# Sheet2.net
KiCad netlist of a schematic drawn in Altium Designer
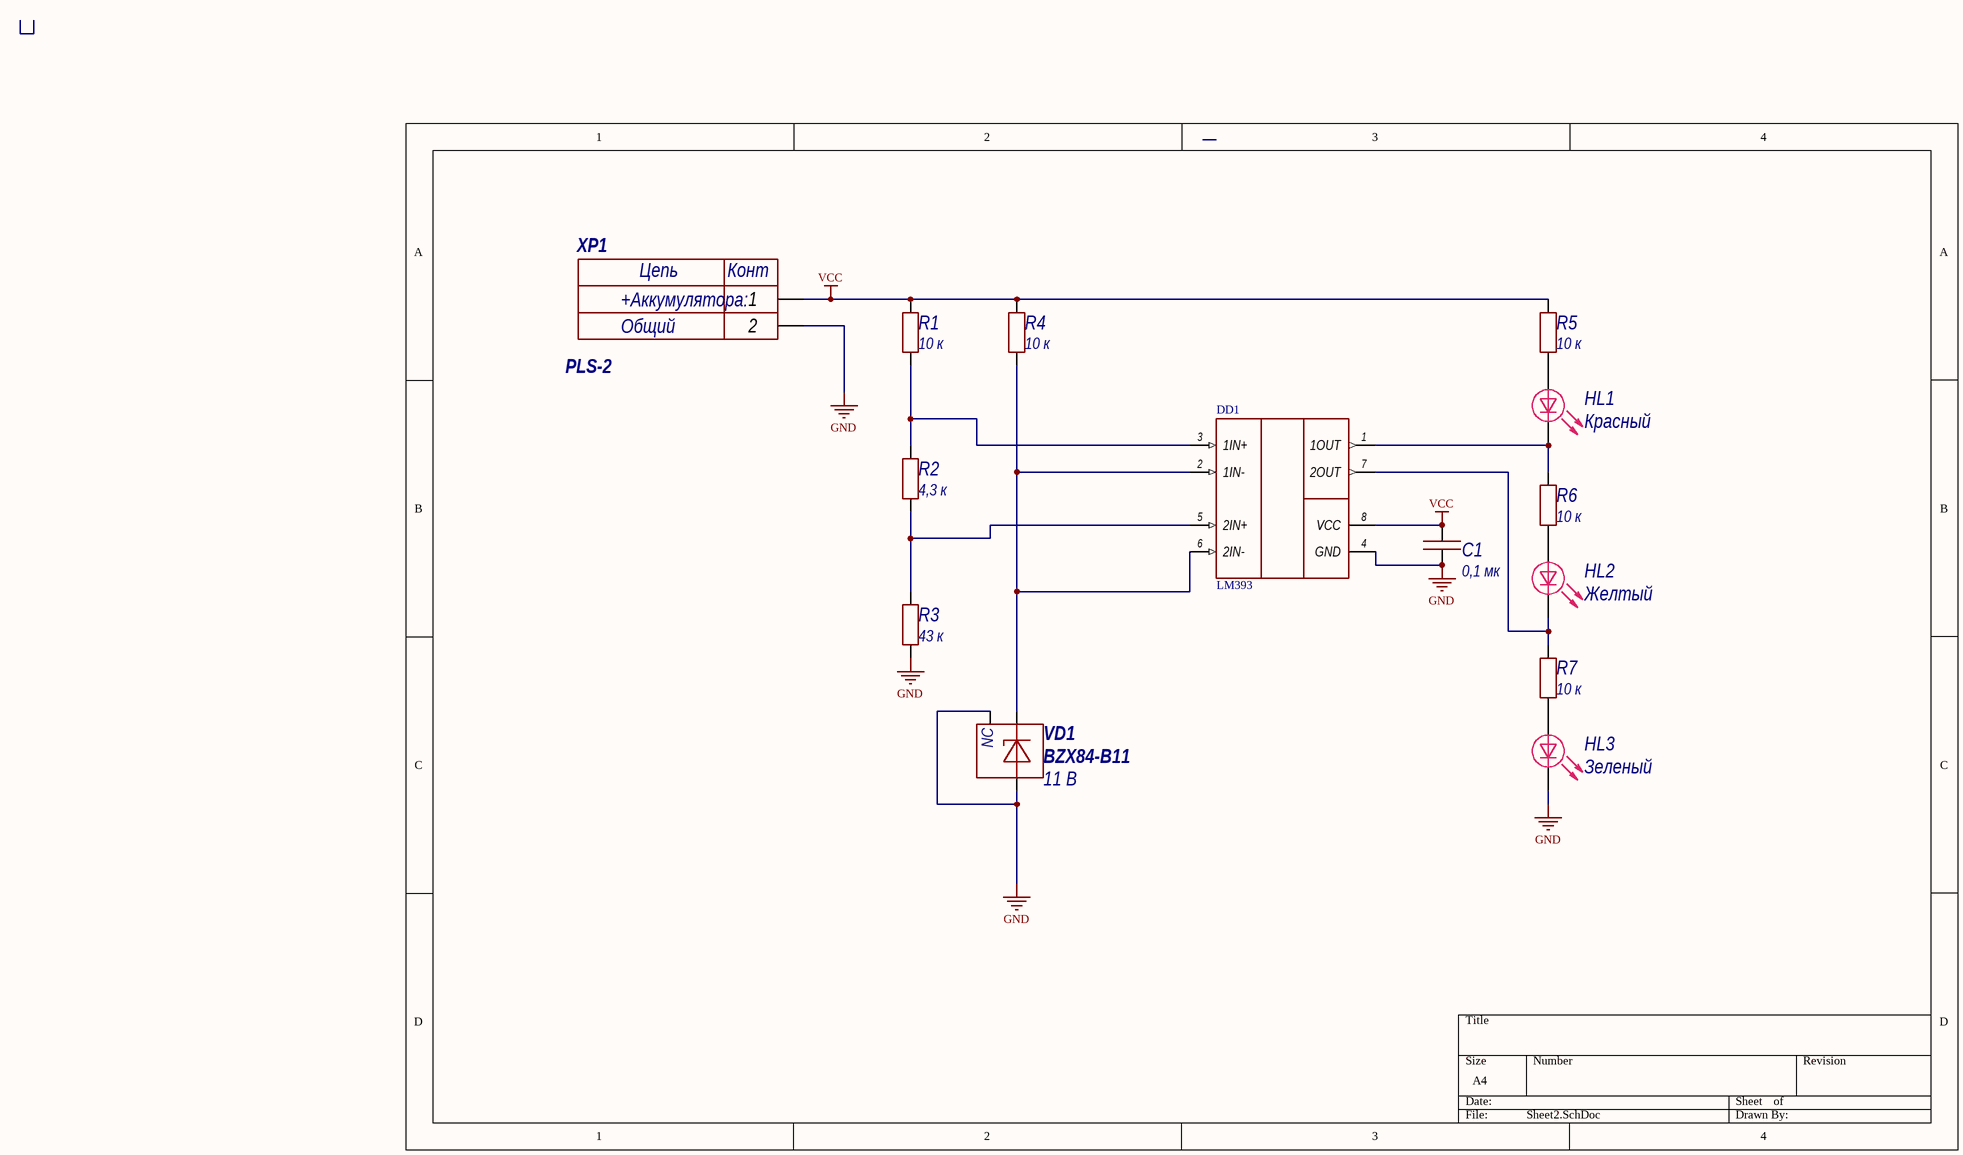
[diagram p0: Sheet2.SchDoc]

(export (version "E")
  (design (tool "Eeschema 10.0.6"))
  (components
    (comp (ref "C1")
      (value "0,1 мк")
      (footprint "0603C")
      (description "Конденсатор 0603C ёмкостью 0,1 мк 10%, 50 В, X7R")
      (fields (field (name "PART NUMBER") "Capacitor_0,1u_10_50V_X7R_0603C") (field (name "TOLERANCE") "10%"))
      (libsource (lib "Hydrolib") (part "Capacitor"))
    )
    (comp (ref "DD1")
      (value "LM393")
      (footprint "SOIC-8")
      (description "Двойной маломощный компаратор напряжения")
      (fields (field (name "MF") "Texas Instruments") (field (name "MP") "LM393D"))
      (libsource (lib "Hydrolib") (part "LM393"))
    )
    (comp (ref "HL1")
      (value "LED")
      (footprint "0805D")
      (description "Светодиод")
      (fields (field (name "COLOR") "Красный"))
      (libsource (lib "Hydrolib") (part "LED"))
    )
    (comp (ref "HL2")
      (value "LED")
      (footprint "0805D")
      (description "Светодиод")
      (fields (field (name "COLOR") "Желтый"))
      (libsource (lib "Hydrolib") (part "LED"))
    )
    (comp (ref "HL3")
      (value "LED")
      (footprint "0805D")
      (description "Светодиод")
      (fields (field (name "COLOR") "Зеленый"))
      (libsource (lib "Hydrolib") (part "LED"))
    )
    (comp (ref "R1")
      (value "10 к")
      (footprint "0603R")
      (description "Резистор номиналом 10 Ом 1%")
      (fields (field (name "PART NUMBER") "Resistor_10_1_0603") (field (name "TOLERANCE") "1%"))
      (libsource (lib "Hydrolib") (part "Resistor"))
    )
    (comp (ref "R2")
      (value "4,3 к")
      (footprint "0603R")
      (description "Резистор номиналом 4,3 Ом 1%")
      (fields (field (name "PART NUMBER") "Resistor_4.3_1_0603") (field (name "TOLERANCE") "1%"))
      (libsource (lib "Hydrolib") (part "Resistor"))
    )
    (comp (ref "R3")
      (value "43 к")
      (footprint "0603R")
      (description "Резистор номиналом 43 кОм 1%")
      (fields (field (name "PART NUMBER") "Resistor_43k_1_0603") (field (name "TOLERANCE") "1%"))
      (libsource (lib "Hydrolib") (part "Resistor"))
    )
    (comp (ref "R4")
      (value "10 к")
      (footprint "0603R")
      (description "Резистор номиналом 4,3 Ом 1%")
      (fields (field (name "PART NUMBER") "Resistor_4.3_1_0603") (field (name "TOLERANCE") "1%"))
      (libsource (lib "Hydrolib") (part "Resistor"))
    )
    (comp (ref "R5")
      (value "10 к")
      (footprint "0603R")
      (description "Резистор номиналом 10 кОм 1%")
      (fields (field (name "PART NUMBER") "Resistor_10k_1_0603") (field (name "TOLERANCE") "1%"))
      (libsource (lib "Hydrolib") (part "Resistor"))
    )
    (comp (ref "R6")
      (value "10 к")
      (footprint "0603R")
      (description "Резистор номиналом 10 кОм 1%")
      (fields (field (name "PART NUMBER") "Resistor_10k_1_0603") (field (name "TOLERANCE") "1%"))
      (libsource (lib "Hydrolib") (part "Resistor"))
    )
    (comp (ref "R7")
      (value "10 к")
      (footprint "0603R")
      (description "Резистор номиналом 10 кОм 1%")
      (fields (field (name "PART NUMBER") "Resistor_10k_1_0603") (field (name "TOLERANCE") "1%"))
      (libsource (lib "Hydrolib") (part "Resistor"))
    )
    (comp (ref "VD1")
      (value "BZX84-B11")
      (footprint "SOT23-3")
      (description "Стабилитрон на 11 В, рассеиваемая мощность 0.25 Вт")
      (fields (field (name "ALTIUM_VALUE") "11 В"))
      (libsource (lib "Hydrolib") (part "Zener_3pin"))
    )
    (comp (ref "XP1")
      (value "PLS-2")
      (footprint "PLS2")
      (description "Гребенка 2 пина")
      (fields (field (name "ОБЩИЙ") "Общий"))
      (libsource (lib "Hydrolib") (part "Conn_2pin"))
    )
  )
  (nets
    (net (code "1") (name "GND") (class "Default")
      (node (ref "C1") (pin "1") (pinfunction "1_1") (pintype "passive"))
      (node (ref "DD1") (pin "4") (pinfunction "GND_4") (pintype "power_in"))
      (node (ref "HL3") (pin "2") (pinfunction "2_2") (pintype "passive"))
      (node (ref "R3") (pin "1") (pinfunction "1_1") (pintype "passive"))
      (node (ref "VD1") (pin "1") (pinfunction "1_1") (pintype "passive"))
      (node (ref "VD1") (pin "2") (pinfunction "2_2") (pintype "passive"))
      (node (ref "XP1") (pin "2") (pinfunction "2_2") (pintype "passive"))
    )
    (net (code "2") (name "Net-(DD1-1IN+)") (class "Default")
      (node (ref "DD1") (pin "3") (pinfunction "1IN+_3") (pintype "input"))
      (node (ref "R1") (pin "1") (pinfunction "1_1") (pintype "passive"))
      (node (ref "R2") (pin "2") (pinfunction "2_2") (pintype "passive"))
    )
    (net (code "3") (name "Net-(DD1-1IN-)") (class "Default")
      (node (ref "DD1") (pin "2") (pinfunction "1IN-_2") (pintype "input"))
      (node (ref "DD1") (pin "6") (pinfunction "2IN-_6") (pintype "input"))
      (node (ref "R4") (pin "1") (pinfunction "1_1") (pintype "passive"))
      (node (ref "VD1") (pin "3") (pinfunction "3_3") (pintype "passive"))
    )
    (net (code "4") (name "Net-(DD1-1OUT)") (class "Default")
      (node (ref "DD1") (pin "1") (pinfunction "1OUT_1") (pintype "output"))
      (node (ref "HL1") (pin "2") (pinfunction "2_2") (pintype "passive"))
      (node (ref "R6") (pin "2") (pinfunction "2_2") (pintype "passive"))
    )
    (net (code "5") (name "Net-(DD1-2IN+)") (class "Default")
      (node (ref "DD1") (pin "5") (pinfunction "2IN+_5") (pintype "input"))
      (node (ref "R2") (pin "1") (pinfunction "1_1") (pintype "passive"))
      (node (ref "R3") (pin "2") (pinfunction "2_2") (pintype "passive"))
    )
    (net (code "6") (name "Net-(DD1-2OUT)") (class "Default")
      (node (ref "DD1") (pin "7") (pinfunction "2OUT_7") (pintype "output"))
      (node (ref "HL2") (pin "2") (pinfunction "2_2") (pintype "passive"))
      (node (ref "R7") (pin "2") (pinfunction "2_2") (pintype "passive"))
    )
    (net (code "7") (name "Net-(HL1-Pad1)") (class "Default")
      (node (ref "HL1") (pin "1") (pinfunction "1_1") (pintype "passive"))
      (node (ref "R5") (pin "1") (pinfunction "1_1") (pintype "passive"))
    )
    (net (code "8") (name "Net-(HL2-Pad1)") (class "Default")
      (node (ref "HL2") (pin "1") (pinfunction "1_1") (pintype "passive"))
      (node (ref "R6") (pin "1") (pinfunction "1_1") (pintype "passive"))
    )
    (net (code "9") (name "Net-(HL3-Pad1)") (class "Default")
      (node (ref "HL3") (pin "1") (pinfunction "1_1") (pintype "passive"))
      (node (ref "R7") (pin "1") (pinfunction "1_1") (pintype "passive"))
    )
    (net (code "10") (name "VCC") (class "Default")
      (node (ref "C1") (pin "2") (pinfunction "2_2") (pintype "passive"))
      (node (ref "DD1") (pin "8") (pinfunction "VCC_8") (pintype "power_in"))
      (node (ref "R1") (pin "2") (pinfunction "2_2") (pintype "passive"))
      (node (ref "R4") (pin "2") (pinfunction "2_2") (pintype "passive"))
      (node (ref "R5") (pin "2") (pinfunction "2_2") (pintype "passive"))
      (node (ref "XP1") (pin "1") (pinfunction "1_1") (pintype "passive"))
    )
  )
)
